# LiPo_fuel_guage.net
KiCad netlist of a schematic drawn in Altium Designer
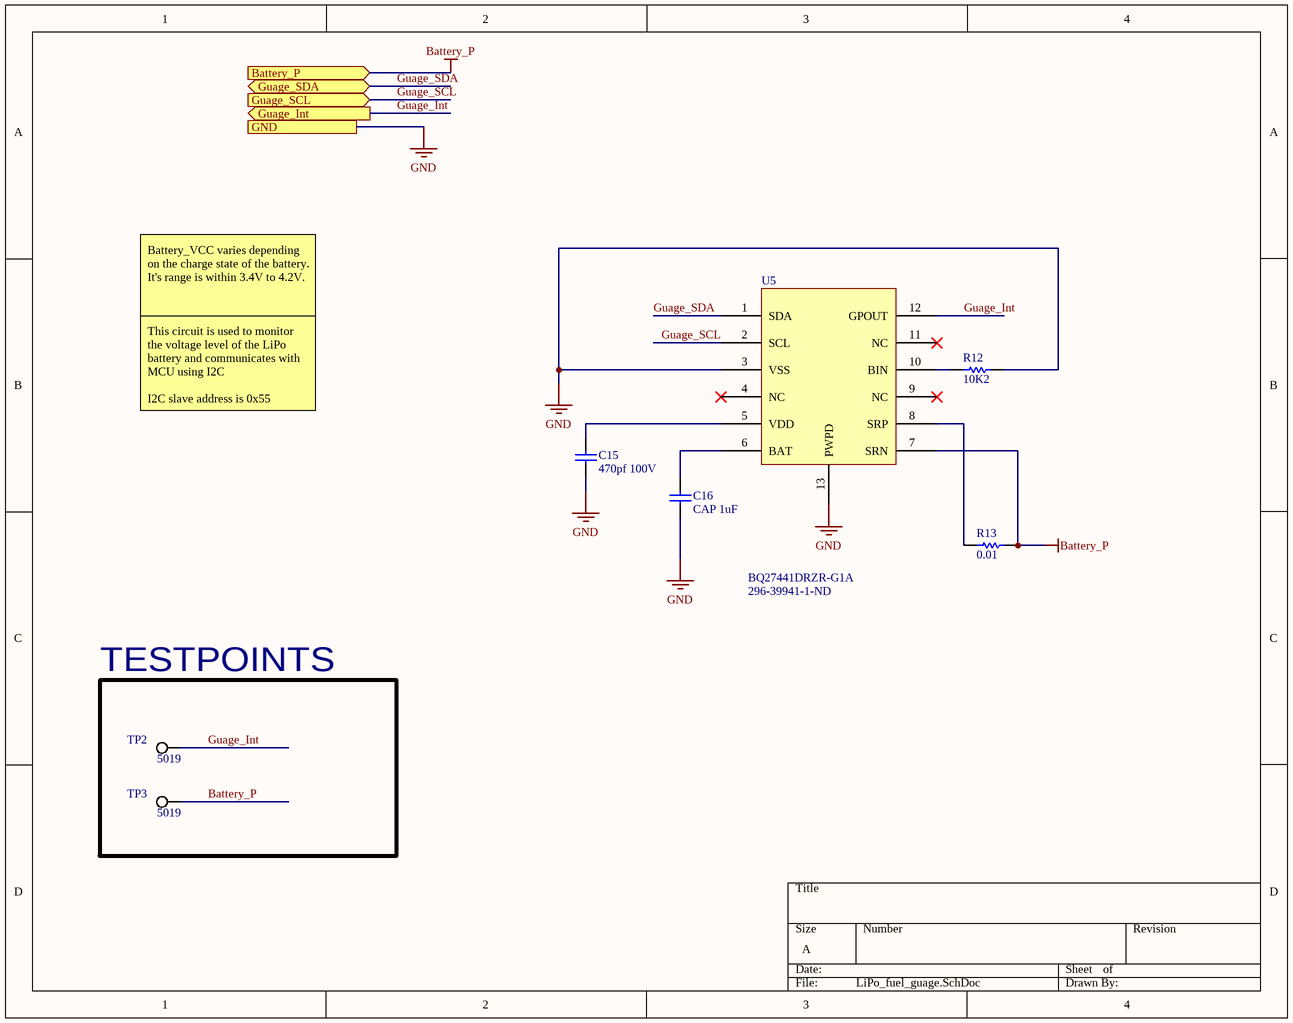
[diagram p0: LiPo_fuel_guage.SchDoc]

(export (version "E")
  (design (tool "Eeschema 10.0.6"))
  (components
    (comp (ref "C15")
      (value "470pf 100V")
      (footprint "CAPC2013X70X45LL10T25")
      (fields (field (name "MANUFACTURER") "Murata") (field (name "PART NUMBER") "GRM2165C2A471JA01D"))
      (libsource (lib "Altium Content Vault") (part "CAP"))
    )
    (comp (ref "C16")
      (value "CAP 1uF")
      (footprint "CAPC0805(2012)100_L")
      (description "CAP 1uF 16V ±20% 0805 (2012 Metric) Thickness 1mm SMD")
      (fields (field (name "TOLERANCE") "Â±20%"))
      (libsource (lib "Altium Content Vault") (part "CAP"))
    )
    (comp (ref "R12")
      (value "10K2")
      (footprint "RESC0805(2012)_L")
      (description "10K2 0.125W 1% 0805 (2012 Metric)  SMD")
      (fields (field (name "TOLERANCE") "1 %") (field (name "POWER") "0.125 W"))
      (libsource (lib "Altium Content Vault") (part "RES"))
    )
    (comp (ref "R13")
      (value "0.01")
      (footprint "RESC3216X70X50LL05T20")
      (fields (field (name "PART NUMBER") "ERJ8BWFR010V") (field (name "MANUFACTURER") "Panasonic"))
      (libsource (lib "Altium Content Vault") (part "RES"))
    )
    (comp (ref "TP2")
      (value "5019")
      (footprint "KSTN-5019_V")
      (description "Test Point, 1 Position SMD, RoHS, Tape and Reel")
      (libsource (lib "Altium Content Vault") (part "TESTPOINT_WHITE"))
    )
    (comp (ref "TP3")
      (value "5019")
      (footprint "KSTN-5019_V")
      (description "Test Point, 1 Position SMD, RoHS, Tape and Reel")
      (libsource (lib "Altium Content Vault") (part "TESTPOINT_WHITE"))
    )
    (comp (ref "U5")
      (value "BQ27441DRZR-G1A")
      (footprint "*SON40P400X250X100-13N")
      (fields
        (field (name "MANUFACTURER") "Texas Instruments")
        (field (name "SUPPLIER PART NUMBER 1") "296-39941-1-ND")
      )
      (libsource (lib "lipo_fuel_gauge") (part "BQ27441DRZR-G1A"))
    )
  )
  (nets
    (net (code "1") (name "/Guage_Int") (class "Default")
      (node (ref "TP2") (pin "1") (pinfunction "1_1") (pintype "passive"))
      (node (ref "U5") (pin "12") (pinfunction "GPOUT_12") (pintype "passive"))
    )
    (net (code "2") (name "/Guage_SCL") (class "Default")
      (node (ref "U5") (pin "2") (pinfunction "SCL_2") (pintype "passive"))
    )
    (net (code "3") (name "/Guage_SDA") (class "Default")
      (node (ref "U5") (pin "1") (pinfunction "SDA_1") (pintype "passive"))
    )
    (net (code "4") (name "Battery_P") (class "Default")
      (node (ref "R13") (pin "2") (pinfunction "2_2") (pintype "passive"))
      (node (ref "TP3") (pin "1") (pinfunction "1_1") (pintype "passive"))
      (node (ref "U5") (pin "7") (pinfunction "SRN_7") (pintype "passive"))
    )
    (net (code "5") (name "GND") (class "Default")
      (node (ref "C15") (pin "1") (pinfunction "1_1") (pintype "passive"))
      (node (ref "C16") (pin "1") (pinfunction "1_1") (pintype "passive"))
      (node (ref "R12") (pin "1") (pinfunction "1_1") (pintype "passive"))
      (node (ref "U5") (pin "13") (pinfunction "PWPD_13") (pintype "passive"))
      (node (ref "U5") (pin "3") (pinfunction "VSS_3") (pintype "passive"))
    )
    (net (code "6") (name "Net-(U5-BAT)") (class "Default")
      (node (ref "C16") (pin "2") (pinfunction "2_2") (pintype "passive"))
      (node (ref "U5") (pin "6") (pinfunction "BAT_6") (pintype "passive"))
    )
    (net (code "7") (name "Net-(U5-BIN)") (class "Default")
      (node (ref "R12") (pin "2") (pinfunction "2_2") (pintype "passive"))
      (node (ref "U5") (pin "10") (pinfunction "BIN_10") (pintype "passive"))
    )
    (net (code "8") (name "Net-(U5-SRP)") (class "Default")
      (node (ref "R13") (pin "1") (pinfunction "1_1") (pintype "passive"))
      (node (ref "U5") (pin "8") (pinfunction "SRP_8") (pintype "passive"))
    )
    (net (code "9") (name "Net-(U5-VDD)") (class "Default")
      (node (ref "C15") (pin "2") (pinfunction "2_2") (pintype "passive"))
      (node (ref "U5") (pin "5") (pinfunction "VDD_5") (pintype "passive"))
    )
    (net (code "10") (name "unconnected-(U5-NC-Pad4)") (class "Default")
      (node (ref "U5") (pin "4") (pinfunction "NC_4") (pintype "passive+no_connect"))
    )
    (net (code "11") (name "unconnected-(U5-NC-Pad9)") (class "Default")
      (node (ref "U5") (pin "9") (pinfunction "NC_9") (pintype "passive+no_connect"))
    )
    (net (code "12") (name "unconnected-(U5-NC-Pad11)") (class "Default")
      (node (ref "U5") (pin "11") (pinfunction "NC_11") (pintype "passive+no_connect"))
    )
  )
)
